# RPi_Lego_Server_Daughter_Board_v1_0A.net
KiCad netlist of a schematic drawn in EAGLE
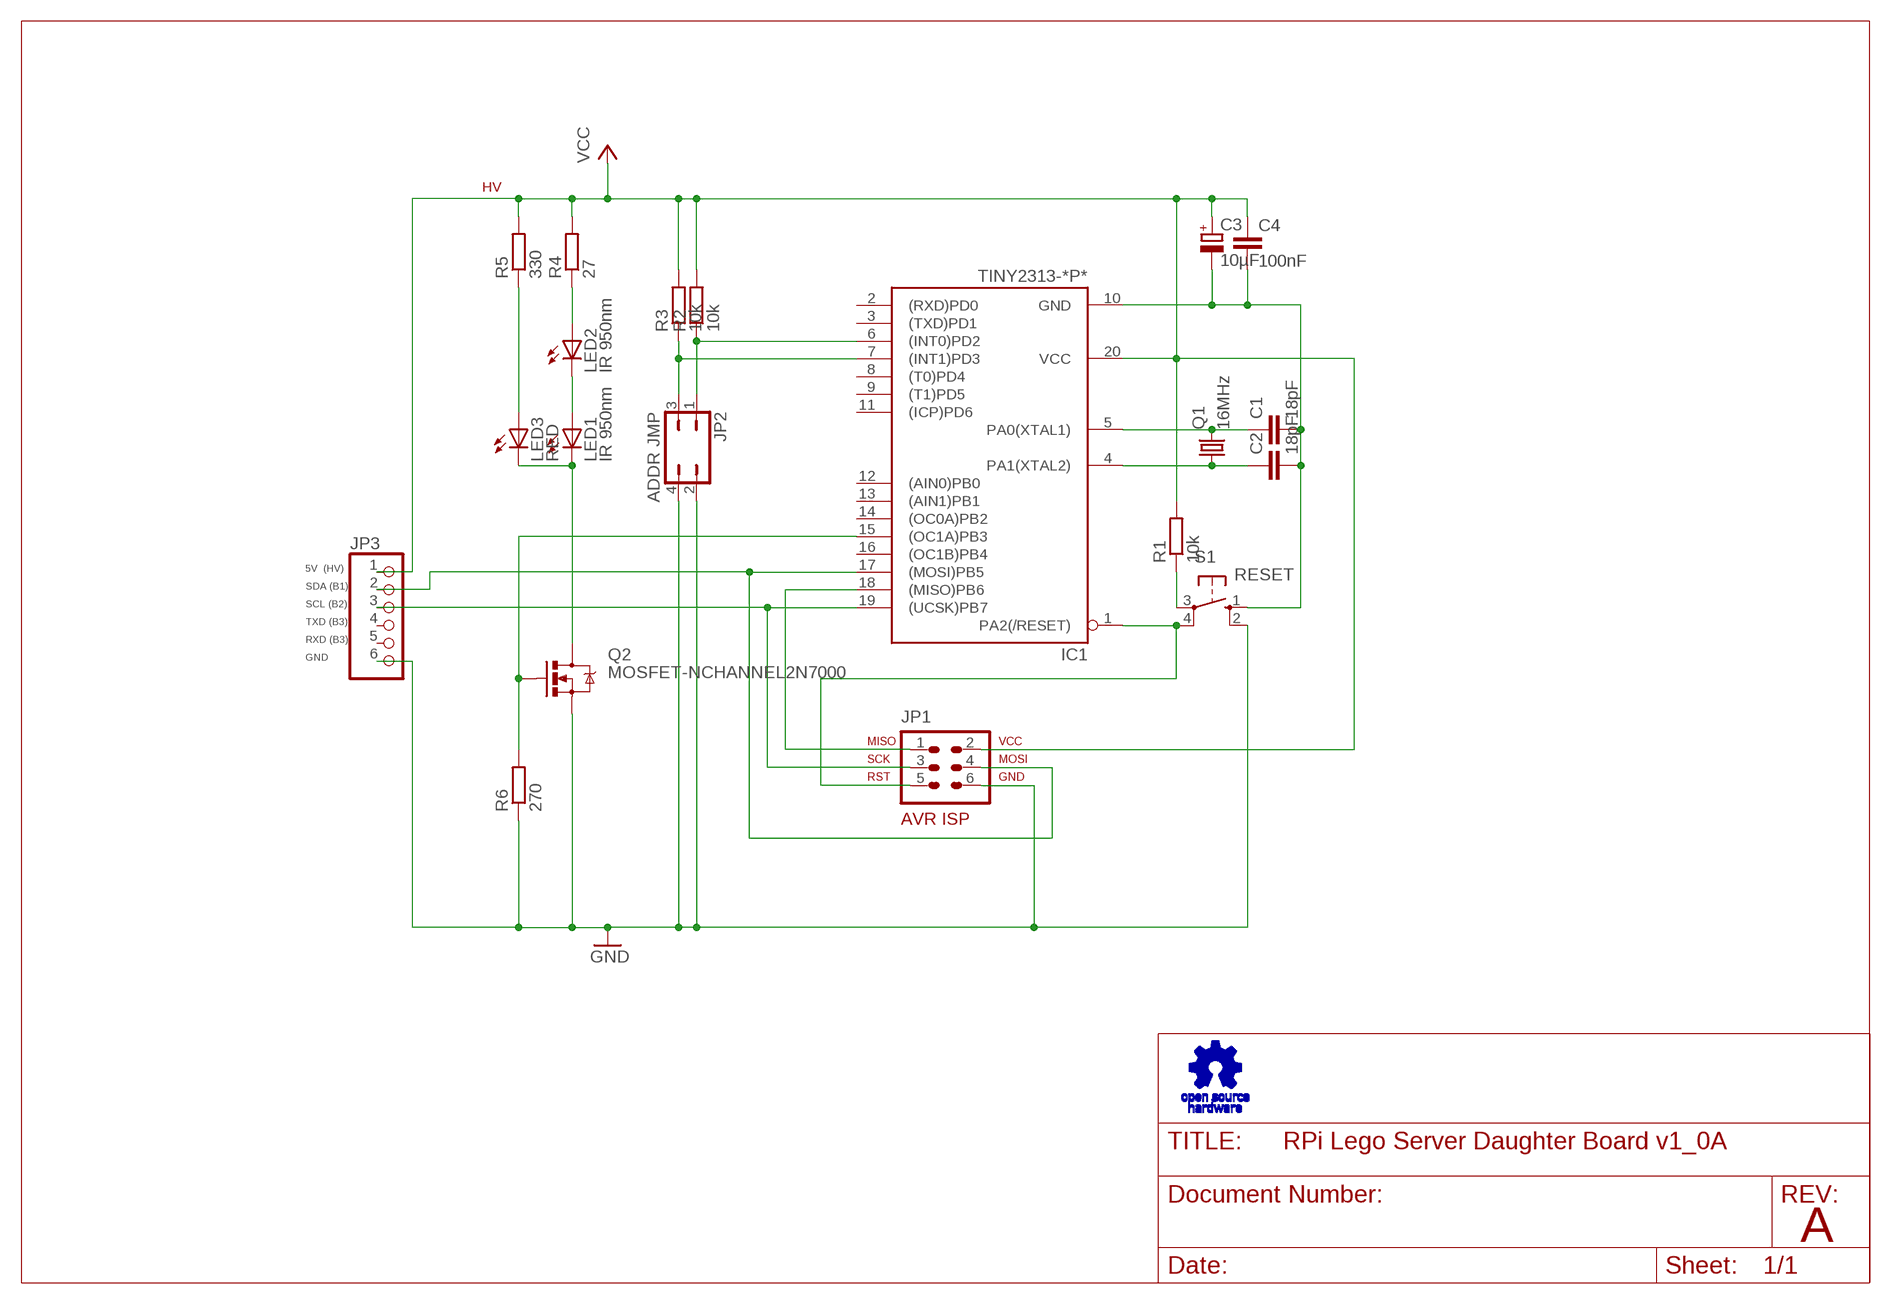
[diagram p0: schematic, sheet 1]

(export (version "E")
  (design (tool "Eeschema 10.0.6"))
  (components
    (comp (ref "C1")
      (value "18pF")
      (footprint "eagle-import:C025-025X050")
      (libsource (lib "eagle-import") (part "C-EU025-025X050"))
    )
    (comp (ref "C2")
      (value "18pF")
      (footprint "eagle-import:C025-025X050")
      (libsource (lib "eagle-import") (part "C-EU025-025X050"))
    )
    (comp (ref "C3")
      (value "10µF")
      (footprint "eagle-import:E2,5-6")
      (libsource (lib "eagle-import") (part "CPOL-EUE2.5-6"))
    )
    (comp (ref "C4")
      (value "100nF")
      (footprint "eagle-import:C050-030X075")
      (libsource (lib "eagle-import") (part "C-EU050-030X075"))
    )
    (comp (ref "IC1")
      (value "TINY2313-*P*")
      (footprint "eagle-import:DIL20")
      (libsource (lib "eagle-import") (part "TINY2313-P"))
    )
    (comp (ref "JP1")
      (value "AVR-ISP-6VERT")
      (footprint "eagle-import:AVR-ISP-6")
      (libsource (lib "eagle-import") (part "AVR-ISP-6VERT"))
    )
    (comp (ref "JP2")
      (value "ADDR JMP")
      (footprint "eagle-import:JP2Q")
      (libsource (lib "eagle-import") (part "JP2Q"))
    )
    (comp (ref "JP3")
      (value "PINHD-1X6")
      (footprint "eagle-import:1X06")
      (libsource (lib "eagle-import") (part "PINHD-1X6"))
    )
    (comp (ref "LED1")
      (value "IR 950nm")
      (footprint "eagle-import:LED5MM")
      (libsource (lib "eagle-import") (part "LED5MM"))
    )
    (comp (ref "LED2")
      (value "IR 950nm")
      (footprint "eagle-import:LED5MM")
      (libsource (lib "eagle-import") (part "LED5MM"))
    )
    (comp (ref "LED3")
      (value "RED")
      (footprint "eagle-import:LED3MM")
      (libsource (lib "eagle-import") (part "LED3MM"))
    )
    (comp (ref "Q1")
      (value "16MHz")
      (footprint "eagle-import:HC49_S")
      (libsource (lib "eagle-import") (part "CRYSTALHC49S"))
    )
    (comp (ref "Q2")
      (value "MOSFET-NCHANNEL2N7000")
      (footprint "eagle-import:TO-92")
      (libsource (lib "eagle-import") (part "MOSFET-NCHANNEL2N7000"))
    )
    (comp (ref "R1")
      (value "10k")
      (footprint "eagle-import:0207_10")
      (libsource (lib "eagle-import") (part "R-EU_0207_10"))
    )
    (comp (ref "R2")
      (value "10k")
      (footprint "eagle-import:0207_10")
      (libsource (lib "eagle-import") (part "R-EU_0207_10"))
    )
    (comp (ref "R3")
      (value "10k")
      (footprint "eagle-import:0207_10")
      (libsource (lib "eagle-import") (part "R-EU_0207_10"))
    )
    (comp (ref "R4")
      (value "27")
      (footprint "eagle-import:0207_10")
      (libsource (lib "eagle-import") (part "R-EU_0207_10"))
    )
    (comp (ref "R5")
      (value "330")
      (footprint "eagle-import:0207_10")
      (libsource (lib "eagle-import") (part "R-EU_0207_10"))
    )
    (comp (ref "R6")
      (value "270")
      (footprint "eagle-import:0207_10")
      (libsource (lib "eagle-import") (part "R-EU_0207_10"))
    )
    (comp (ref "S1")
      (value "RESET")
      (footprint "eagle-import:B3F-10XX")
      (fields (field (name "MPN") "B3F-1000"))
      (libsource (lib "eagle-import") (part "10-XX"))
    )
  )
  (nets
    (net (code "1") (name "GND") (class "Default")
      (node (ref "C1") (pin "2") (pinfunction "2_2") (pintype "passive"))
      (node (ref "C2") (pin "2") (pinfunction "2_2") (pintype "passive"))
      (node (ref "C3") (pin "-") (pinfunction "-_-") (pintype "passive"))
      (node (ref "C4") (pin "2") (pinfunction "2_2") (pintype "passive"))
      (node (ref "IC1") (pin "10") (pinfunction "GND_10") (pintype "power_in"))
      (node (ref "JP1") (pin "6") (pinfunction "6_6") (pintype "passive"))
      (node (ref "JP2") (pin "2") (pinfunction "2_2") (pintype "passive"))
      (node (ref "JP2") (pin "4") (pinfunction "4_4") (pintype "passive"))
      (node (ref "JP3") (pin "6") (pinfunction "6_6") (pintype "passive"))
      (node (ref "Q2") (pin "1") (pinfunction "S_1") (pintype "passive"))
      (node (ref "R6") (pin "1") (pinfunction "1_1") (pintype "passive"))
      (node (ref "S1") (pin "1") (pinfunction "S_1") (pintype "passive"))
      (node (ref "S1") (pin "2") (pinfunction "S1_2") (pintype "passive"))
    )
    (net (code "2") (name "Net-(IC1-(INT0)PD2)") (class "Default")
      (node (ref "IC1") (pin "6") (pinfunction "(INT0)PD2_6") (pintype "bidirectional"))
      (node (ref "JP2") (pin "1") (pinfunction "1_1") (pintype "passive"))
      (node (ref "R2") (pin "1") (pinfunction "1_1") (pintype "passive"))
    )
    (net (code "3") (name "Net-(IC1-(INT1)PD3)") (class "Default")
      (node (ref "IC1") (pin "7") (pinfunction "(INT1)PD3_7") (pintype "bidirectional"))
      (node (ref "JP2") (pin "3") (pinfunction "3_3") (pintype "passive"))
      (node (ref "R3") (pin "1") (pinfunction "1_1") (pintype "passive"))
    )
    (net (code "4") (name "Net-(IC1-(MISO)PB6)") (class "Default")
      (node (ref "IC1") (pin "18") (pinfunction "(MISO)PB6_18") (pintype "bidirectional"))
      (node (ref "JP1") (pin "1") (pinfunction "1_1") (pintype "passive"))
    )
    (net (code "5") (name "Net-(IC1-(MOSI)PB5)") (class "Default")
      (node (ref "IC1") (pin "17") (pinfunction "(MOSI)PB5_17") (pintype "bidirectional"))
      (node (ref "JP1") (pin "4") (pinfunction "4_4") (pintype "passive"))
      (node (ref "JP3") (pin "2") (pinfunction "2_2") (pintype "passive"))
    )
    (net (code "6") (name "Net-(IC1-(OC1A)PB3)") (class "Default")
      (node (ref "IC1") (pin "15") (pinfunction "(OC1A)PB3_15") (pintype "bidirectional"))
      (node (ref "Q2") (pin "2") (pinfunction "G_2") (pintype "passive"))
      (node (ref "R6") (pin "2") (pinfunction "2_2") (pintype "passive"))
    )
    (net (code "7") (name "Net-(IC1-(UCSK)PB7)") (class "Default")
      (node (ref "IC1") (pin "19") (pinfunction "(UCSK)PB7_19") (pintype "bidirectional"))
      (node (ref "JP1") (pin "3") (pinfunction "3_3") (pintype "passive"))
      (node (ref "JP3") (pin "3") (pinfunction "3_3") (pintype "passive"))
    )
    (net (code "8") (name "Net-(IC1-PA0(XTAL1))") (class "Default")
      (node (ref "C1") (pin "1") (pinfunction "1_1") (pintype "passive"))
      (node (ref "IC1") (pin "5") (pinfunction "PA0(XTAL1)_5") (pintype "bidirectional"))
      (node (ref "Q1") (pin "2") (pinfunction "2_2") (pintype "passive"))
    )
    (net (code "9") (name "Net-(IC1-PA1(XTAL2))") (class "Default")
      (node (ref "C2") (pin "1") (pinfunction "1_1") (pintype "passive"))
      (node (ref "IC1") (pin "4") (pinfunction "PA1(XTAL2)_4") (pintype "bidirectional"))
      (node (ref "Q1") (pin "1") (pinfunction "1_1") (pintype "passive"))
    )
    (net (code "10") (name "Net-(IC1-PA2({slash}RESET))") (class "Default")
      (node (ref "IC1") (pin "1") (pinfunction "PA2(/RESET)_1") (pintype "input"))
      (node (ref "JP1") (pin "5") (pinfunction "5_5") (pintype "passive"))
      (node (ref "S1") (pin "4") (pinfunction "P1_4") (pintype "passive"))
    )
    (net (code "11") (name "Net-(LED1-C)") (class "Default")
      (node (ref "LED1") (pin "K") (pinfunction "C_K") (pintype "passive"))
      (node (ref "LED3") (pin "K") (pinfunction "C_K") (pintype "passive"))
      (node (ref "Q2") (pin "3") (pinfunction "D_3") (pintype "passive"))
    )
    (net (code "12") (name "Net-(LED2-C)") (class "Default")
      (node (ref "LED1") (pin "A") (pinfunction "A_A") (pintype "passive"))
      (node (ref "LED2") (pin "K") (pinfunction "C_K") (pintype "passive"))
    )
    (net (code "13") (name "Net-(LED2-PadA)") (class "Default")
      (node (ref "LED2") (pin "A") (pinfunction "A_A") (pintype "passive"))
      (node (ref "R4") (pin "1") (pinfunction "1_1") (pintype "passive"))
    )
    (net (code "14") (name "Net-(LED3-PadA)") (class "Default")
      (node (ref "LED3") (pin "A") (pinfunction "A_A") (pintype "passive"))
      (node (ref "R5") (pin "1") (pinfunction "1_1") (pintype "passive"))
    )
    (net (code "15") (name "Net-(S1-P)") (class "Default")
      (node (ref "R1") (pin "1") (pinfunction "1_1") (pintype "passive"))
      (node (ref "S1") (pin "3") (pinfunction "P_3") (pintype "passive"))
    )
    (net (code "16") (name "VCC") (class "Default")
      (node (ref "C3") (pin "+") (pinfunction "+_+") (pintype "passive"))
      (node (ref "C4") (pin "1") (pinfunction "1_1") (pintype "passive"))
      (node (ref "IC1") (pin "20") (pinfunction "VCC_20") (pintype "power_in"))
      (node (ref "JP1") (pin "2") (pinfunction "2_2") (pintype "passive"))
      (node (ref "JP3") (pin "1") (pinfunction "1_1") (pintype "passive"))
      (node (ref "R1") (pin "2") (pinfunction "2_2") (pintype "passive"))
      (node (ref "R2") (pin "2") (pinfunction "2_2") (pintype "passive"))
      (node (ref "R3") (pin "2") (pinfunction "2_2") (pintype "passive"))
      (node (ref "R4") (pin "2") (pinfunction "2_2") (pintype "passive"))
      (node (ref "R5") (pin "2") (pinfunction "2_2") (pintype "passive"))
    )
    (net (code "17") (name "unconnected-(IC1-(AIN0)PB0-Pad12)") (class "Default")
      (node (ref "IC1") (pin "12") (pinfunction "(AIN0)PB0_12") (pintype "bidirectional"))
    )
    (net (code "18") (name "unconnected-(IC1-(AIN1)PB1-Pad13)") (class "Default")
      (node (ref "IC1") (pin "13") (pinfunction "(AIN1)PB1_13") (pintype "bidirectional"))
    )
    (net (code "19") (name "unconnected-(IC1-(ICP)PD6-Pad11)") (class "Default")
      (node (ref "IC1") (pin "11") (pinfunction "(ICP)PD6_11") (pintype "bidirectional"))
    )
    (net (code "20") (name "unconnected-(IC1-(OC0A)PB2-Pad14)") (class "Default")
      (node (ref "IC1") (pin "14") (pinfunction "(OC0A)PB2_14") (pintype "bidirectional"))
    )
    (net (code "21") (name "unconnected-(IC1-(OC1B)PB4-Pad16)") (class "Default")
      (node (ref "IC1") (pin "16") (pinfunction "(OC1B)PB4_16") (pintype "bidirectional"))
    )
    (net (code "22") (name "unconnected-(IC1-(RXD)PD0-Pad2)") (class "Default")
      (node (ref "IC1") (pin "2") (pinfunction "(RXD)PD0_2") (pintype "bidirectional"))
    )
    (net (code "23") (name "unconnected-(IC1-(T0)PD4-Pad8)") (class "Default")
      (node (ref "IC1") (pin "8") (pinfunction "(T0)PD4_8") (pintype "bidirectional"))
    )
    (net (code "24") (name "unconnected-(IC1-(T1)PD5-Pad9)") (class "Default")
      (node (ref "IC1") (pin "9") (pinfunction "(T1)PD5_9") (pintype "bidirectional"))
    )
    (net (code "25") (name "unconnected-(IC1-(TXD)PD1-Pad3)") (class "Default")
      (node (ref "IC1") (pin "3") (pinfunction "(TXD)PD1_3") (pintype "bidirectional"))
    )
    (net (code "26") (name "unconnected-(JP3-Pad4)") (class "Default")
      (node (ref "JP3") (pin "4") (pinfunction "4_4") (pintype "passive"))
    )
    (net (code "27") (name "unconnected-(JP3-Pad5)") (class "Default")
      (node (ref "JP3") (pin "5") (pinfunction "5_5") (pintype "passive"))
    )
  )
)
